# ASM2027-Rev3.net
KiCad netlist of a schematic drawn in EAGLE
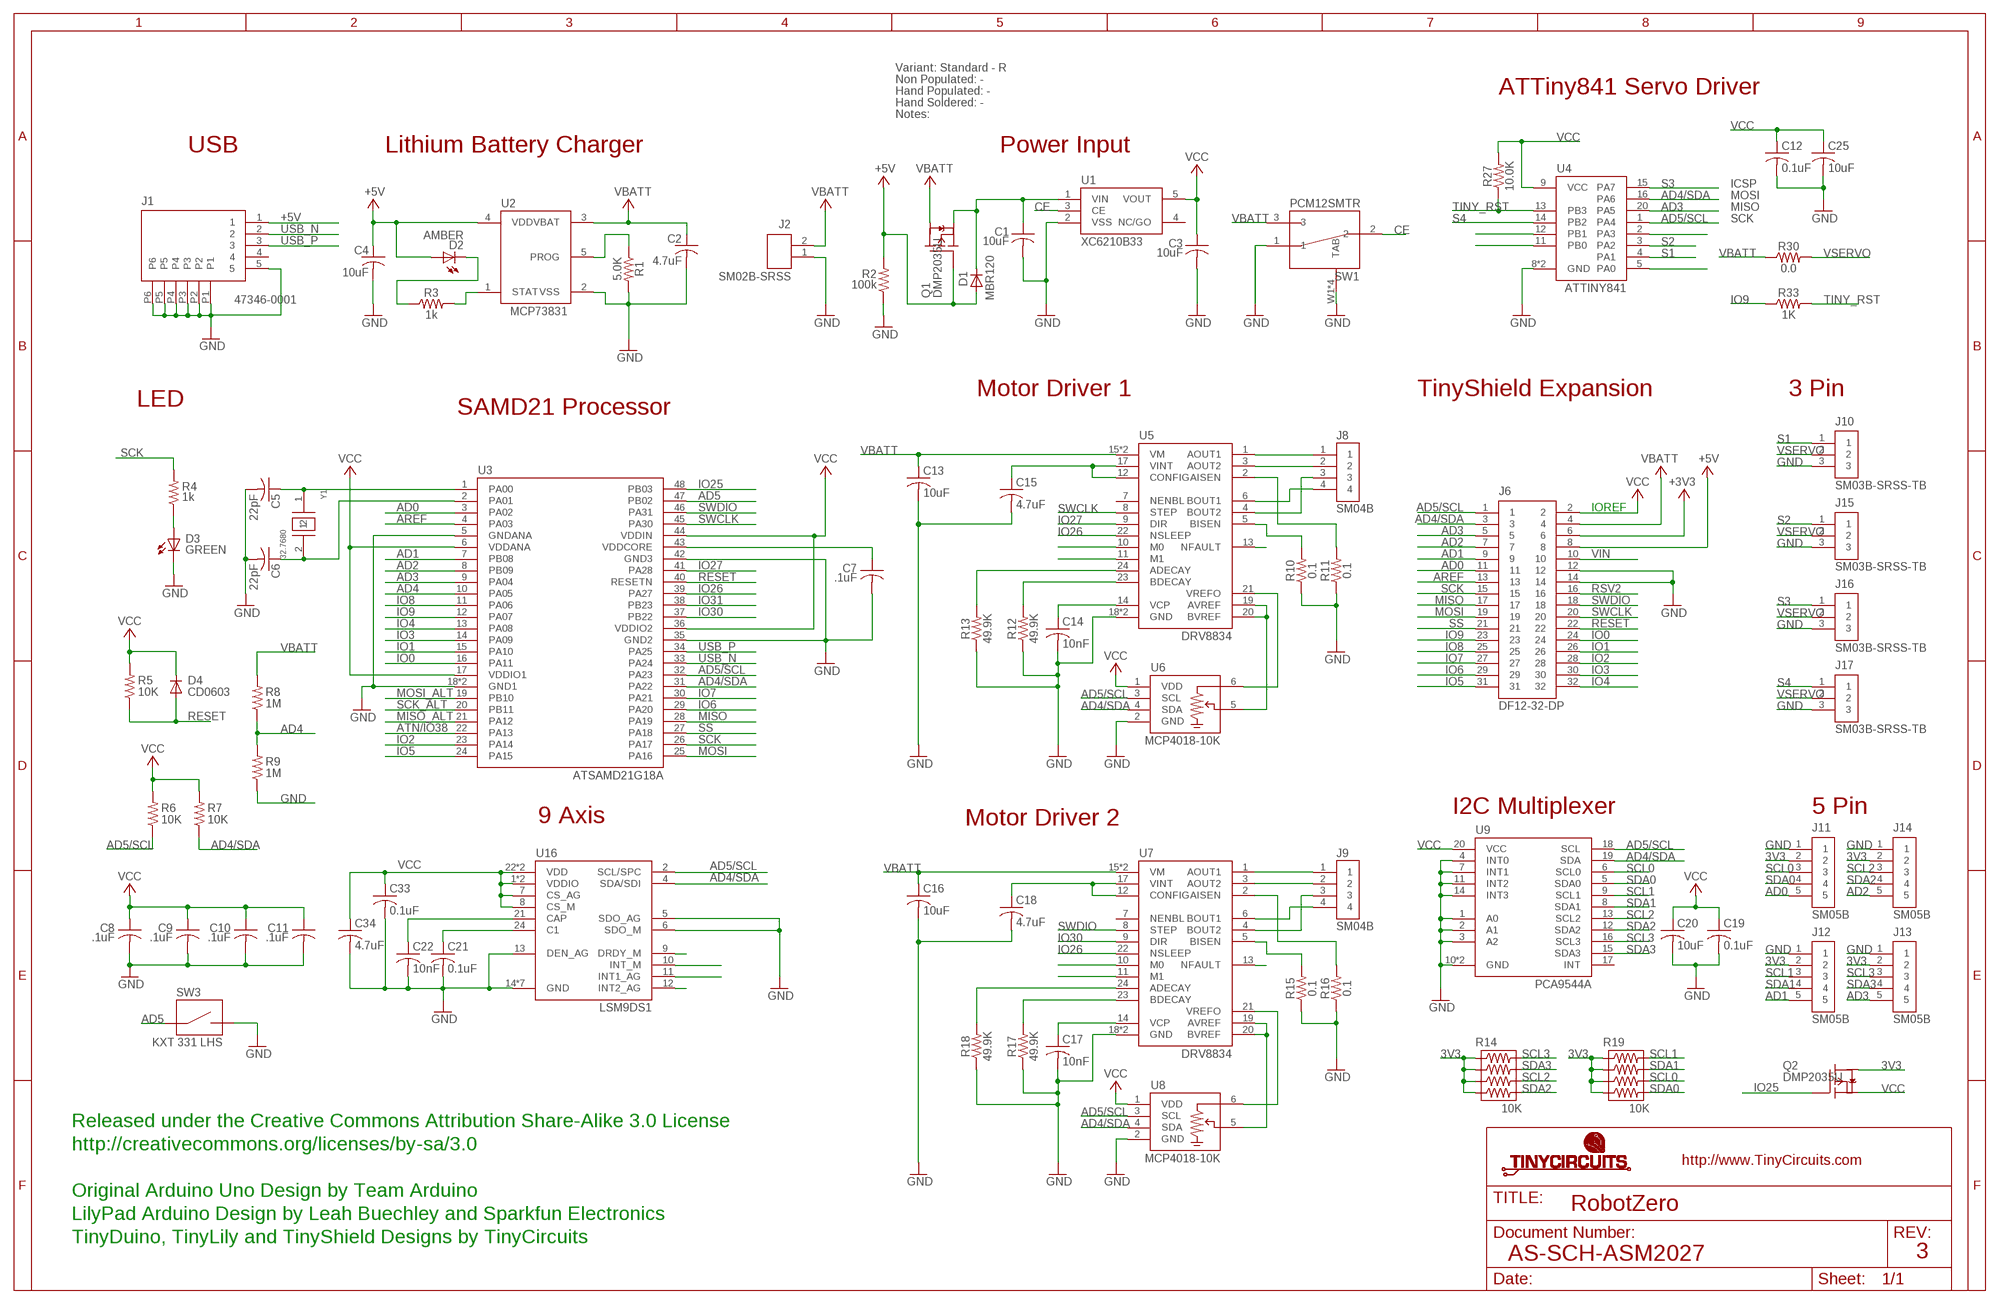
[diagram p0: schematic, sheet 1]

(export (version "E")
  (design (tool "Eeschema 10.0.6"))
  (components
    (comp (ref "C1")
      (value "10uF")
      (footprint "eagle-import:C0603")
      (fields (field (name "PARTNO") "AS-ITM-00002") (field (name "PARTNO_1") "AS-ITM-00002"))
      (libsource (lib "eagle-import") (part "AS-ITM-00002"))
    )
    (comp (ref "C2")
      (value "4.7uF")
      (footprint "eagle-import:C0603")
      (fields (field (name "PARTNO") "AS-ITM-00088") (field (name "PARTNO_1") "AS-ITM-00088"))
      (libsource (lib "eagle-import") (part "AS-ITM-00088"))
    )
    (comp (ref "C3")
      (value "10uF")
      (footprint "eagle-import:C0603")
      (fields (field (name "PARTNO") "AS-ITM-00002") (field (name "PARTNO_1") "AS-ITM-00002"))
      (libsource (lib "eagle-import") (part "AS-ITM-00002"))
    )
    (comp (ref "C4")
      (value "10uF")
      (footprint "eagle-import:C0603")
      (fields (field (name "PARTNO") "AS-ITM-00002") (field (name "PARTNO_1") "AS-ITM-00002"))
      (libsource (lib "eagle-import") (part "AS-ITM-00002"))
    )
    (comp (ref "C5")
      (value "22pF")
      (footprint "eagle-import:C0402")
      (fields (field (name "PARTNO") "AS-ITM-00211") (field (name "PARTNO_1") "AS-ITM-00211"))
      (libsource (lib "eagle-import") (part "AS-ITM-00211"))
    )
    (comp (ref "C6")
      (value "22pF")
      (footprint "eagle-import:C0402")
      (fields (field (name "PARTNO") "AS-ITM-00211") (field (name "PARTNO_1") "AS-ITM-00211"))
      (libsource (lib "eagle-import") (part "AS-ITM-00211"))
    )
    (comp (ref "C7")
      (value ".1uF")
      (footprint "eagle-import:C0402")
      (fields (field (name "PARTNO") "AS-ITM-00008") (field (name "PARTNO_1") "AS-ITM-00008"))
      (libsource (lib "eagle-import") (part "AS-ITM-00008"))
    )
    (comp (ref "C8")
      (value ".1uF")
      (footprint "eagle-import:C0402")
      (fields (field (name "PARTNO") "AS-ITM-00008") (field (name "PARTNO_1") "AS-ITM-00008"))
      (libsource (lib "eagle-import") (part "AS-ITM-00008"))
    )
    (comp (ref "C9")
      (value ".1uF")
      (footprint "eagle-import:C0402")
      (fields (field (name "PARTNO") "AS-ITM-00008") (field (name "PARTNO_1") "AS-ITM-00008"))
      (libsource (lib "eagle-import") (part "AS-ITM-00008"))
    )
    (comp (ref "C10")
      (value ".1uF")
      (footprint "eagle-import:C0402")
      (fields (field (name "PARTNO") "AS-ITM-00008") (field (name "PARTNO_1") "AS-ITM-00008"))
      (libsource (lib "eagle-import") (part "AS-ITM-00008"))
    )
    (comp (ref "C11")
      (value ".1uF")
      (footprint "eagle-import:C0402")
      (fields (field (name "PARTNO") "AS-ITM-00008") (field (name "PARTNO_1") "AS-ITM-00008"))
      (libsource (lib "eagle-import") (part "AS-ITM-00008"))
    )
    (comp (ref "C12")
      (value "0.1uF")
      (footprint "eagle-import:C0402")
      (fields (field (name "PARTNO") "AS-ITM-00008"))
      (libsource (lib "eagle-import") (part "AS-ITM-00008"))
    )
    (comp (ref "C13")
      (value "10uF")
      (footprint "eagle-import:C0603")
      (fields (field (name "PARTNO") "AS-ITM-00002"))
      (libsource (lib "eagle-import") (part "AS-ITM-00002"))
    )
    (comp (ref "C14")
      (value "10nF")
      (footprint "eagle-import:C0402")
      (fields (field (name "PARTNO") "AS-ITM-00084"))
      (libsource (lib "eagle-import") (part "AS-ITM-00084"))
    )
    (comp (ref "C15")
      (value "4.7uF")
      (footprint "eagle-import:C0402")
      (fields (field (name "PARTNO") "AS-ITM-00242"))
      (libsource (lib "eagle-import") (part "AS-ITM-00242"))
    )
    (comp (ref "C16")
      (value "10uF")
      (footprint "eagle-import:C0603")
      (fields (field (name "PARTNO") "AS-ITM-00002"))
      (libsource (lib "eagle-import") (part "AS-ITM-00002"))
    )
    (comp (ref "C17")
      (value "10nF")
      (footprint "eagle-import:C0402")
      (fields (field (name "PARTNO") "AS-ITM-00084"))
      (libsource (lib "eagle-import") (part "AS-ITM-00084"))
    )
    (comp (ref "C18")
      (value "4.7uF")
      (footprint "eagle-import:C0402")
      (fields (field (name "PARTNO") "AS-ITM-00242"))
      (libsource (lib "eagle-import") (part "AS-ITM-00242"))
    )
    (comp (ref "C19")
      (value "0.1uF")
      (footprint "eagle-import:C0402")
      (fields (field (name "PARTNO") "AS-ITM-00008"))
      (libsource (lib "eagle-import") (part "AS-ITM-00008"))
    )
    (comp (ref "C20")
      (value "10uF")
      (footprint "eagle-import:C0603")
      (fields (field (name "PARTNO") "AS-ITM-00002"))
      (libsource (lib "eagle-import") (part "AS-ITM-00002"))
    )
    (comp (ref "C21")
      (value "0.1uF")
      (footprint "eagle-import:C0402")
      (fields (field (name "PARTNO") "AS-ITM-00008"))
      (libsource (lib "eagle-import") (part "AS-ITM-00008"))
    )
    (comp (ref "C22")
      (value "10nF")
      (footprint "eagle-import:C0402")
      (fields (field (name "PARTNO") "AS-ITM-00084"))
      (libsource (lib "eagle-import") (part "AS-ITM-00084"))
    )
    (comp (ref "C25")
      (value "10uF")
      (footprint "eagle-import:C0805")
      (fields (field (name "PARTNO") "AS-ITM-00045"))
      (libsource (lib "eagle-import") (part "AS-ITM-00045"))
    )
    (comp (ref "C33")
      (value "0.1uF")
      (footprint "eagle-import:C0402")
      (fields (field (name "PARTNO") "AS-ITM-00008") (field (name "PARTNO_1") "AS-ITM-00008"))
      (libsource (lib "eagle-import") (part "AS-ITM-00008"))
    )
    (comp (ref "C34")
      (value "4.7uF")
      (footprint "eagle-import:C0402")
      (fields (field (name "PARTNO") "AS-ITM-00242") (field (name "PARTNO_1") "AS-ITM-00242"))
      (libsource (lib "eagle-import") (part "AS-ITM-00242"))
    )
    (comp (ref "D1")
      (value "MBR120")
      (footprint "eagle-import:SOD-123FL")
      (fields (field (name "PARTNO") "AS-ITM-00111"))
      (libsource (lib "eagle-import") (part "AS-ITM-00111"))
    )
    (comp (ref "D2")
      (value "AMBER")
      (footprint "eagle-import:0402_LED")
      (fields (field (name "PARTNO") "AS-ITM-00058") (field (name "PARTNO_1") "AS-ITM-00058"))
      (libsource (lib "eagle-import") (part "AS-ITM-00058"))
    )
    (comp (ref "D3")
      (value "GREEN")
      (footprint "eagle-import:LNJ_LED")
      (fields (field (name "PARTNO") "AS-ITM-00011") (field (name "PARTNO_1") "AS-ITM-00011"))
      (libsource (lib "eagle-import") (part "AS-ITM-00011"))
    )
    (comp (ref "D4")
      (value "CD0603")
      (footprint "eagle-import:0603")
      (fields (field (name "PARTNO") "AS-ITM-00009") (field (name "PARTNO_1") "AS-ITM-00009"))
      (libsource (lib "eagle-import") (part "AS-ITM-00009"))
    )
    (comp (ref "J1")
      (value "47346-0001")
      (footprint "eagle-import:MICRO_USB")
      (fields (field (name "PARTNO") "AS-ITM-00021"))
      (libsource (lib "eagle-import") (part "AS-ITM-00021"))
    )
    (comp (ref "J2")
      (value "SM02B-SRSS")
      (footprint "eagle-import:JST_SH_2X1")
      (fields (field (name "PARTNO") "AS-ITM-00231"))
      (libsource (lib "eagle-import") (part "AS-ITM-00231"))
    )
    (comp (ref "J6")
      (value "DF12-32-DP")
      (footprint "eagle-import:DF12-32-DP")
      (fields (field (name "PARTNO") "AS-ITM-00015") (field (name "PARTNO_1") "AS-ITM-00015"))
      (libsource (lib "eagle-import") (part "AS-ITM-00015"))
    )
    (comp (ref "J8")
      (value "SM04B")
      (footprint "eagle-import:JST_SH_4X1")
      (fields (field (name "PARTNO") "AS-ITM-00395") (field (name "PARTNO_1") "AS-ITM-00395"))
      (libsource (lib "eagle-import") (part "AS-ITM-00395"))
    )
    (comp (ref "J9")
      (value "SM04B")
      (footprint "eagle-import:JST_SH_4X1")
      (fields (field (name "PARTNO") "AS-ITM-00395") (field (name "PARTNO_1") "AS-ITM-00395"))
      (libsource (lib "eagle-import") (part "AS-ITM-00395"))
    )
    (comp (ref "J10")
      (value "SM03B-SRSS-TB")
      (footprint "eagle-import:JST_SH_3X1_VERT")
      (fields (field (name "PARTNO") "AS-ITM-00471") (field (name "PARTNO_1") "AS-ITM-00471"))
      (libsource (lib "eagle-import") (part "AS-ITM-00471"))
    )
    (comp (ref "J11")
      (value "SM05B")
      (footprint "eagle-import:JST_SH_5X1_VERT")
      (fields (field (name "PARTNO") "AS-ITM-00391") (field (name "PARTNO_1") "AS-ITM-00391"))
      (libsource (lib "eagle-import") (part "AS-ITM-00391"))
    )
    (comp (ref "J12")
      (value "SM05B")
      (footprint "eagle-import:JST_SH_5X1_VERT")
      (fields (field (name "PARTNO") "AS-ITM-00391") (field (name "PARTNO_1") "AS-ITM-00391"))
      (libsource (lib "eagle-import") (part "AS-ITM-00391"))
    )
    (comp (ref "J13")
      (value "SM05B")
      (footprint "eagle-import:JST_SH_5X1_VERT")
      (fields (field (name "PARTNO") "AS-ITM-00391") (field (name "PARTNO_1") "AS-ITM-00391"))
      (libsource (lib "eagle-import") (part "AS-ITM-00391"))
    )
    (comp (ref "J14")
      (value "SM05B")
      (footprint "eagle-import:JST_SH_5X1_VERT")
      (fields (field (name "PARTNO") "AS-ITM-00391") (field (name "PARTNO_1") "AS-ITM-00391"))
      (libsource (lib "eagle-import") (part "AS-ITM-00391"))
    )
    (comp (ref "J15")
      (value "SM03B-SRSS-TB")
      (footprint "eagle-import:JST_SH_3X1_VERT")
      (fields (field (name "PARTNO") "AS-ITM-00471") (field (name "PARTNO_1") "AS-ITM-00471"))
      (libsource (lib "eagle-import") (part "AS-ITM-00471"))
    )
    (comp (ref "J16")
      (value "SM03B-SRSS-TB")
      (footprint "eagle-import:JST_SH_3X1_VERT")
      (fields (field (name "PARTNO") "AS-ITM-00471") (field (name "PARTNO_1") "AS-ITM-00471"))
      (libsource (lib "eagle-import") (part "AS-ITM-00471"))
    )
    (comp (ref "J17")
      (value "SM03B-SRSS-TB")
      (footprint "eagle-import:JST_SH_3X1_VERT")
      (fields (field (name "PARTNO") "AS-ITM-00471") (field (name "PARTNO_1") "AS-ITM-00471"))
      (libsource (lib "eagle-import") (part "AS-ITM-00471"))
    )
    (comp (ref "Q1")
      (value "DMP2035U")
      (footprint "eagle-import:SOT23A")
      (fields (field (name "PARTNO") "AS-ITM-00024") (field (name "PARTNO_1") "AS-ITM-00024"))
      (libsource (lib "eagle-import") (part "AS-ITM-00024A"))
    )
    (comp (ref "Q2")
      (value "DMP2035U")
      (footprint "eagle-import:SOT23A")
      (fields (field (name "PARTNO") "AS-ITM-00024") (field (name "PARTNO_1") "AS-ITM-00024"))
      (libsource (lib "eagle-import") (part "AS-ITM-00024A"))
    )
    (comp (ref "R1")
      (value "5.0K")
      (footprint "eagle-import:0402")
      (fields (field (name "PARTNO") "AS-ITM-00289") (field (name "PARTNO_1") "AS-ITM-00289"))
      (libsource (lib "eagle-import") (part "AS-ITM-00289"))
    )
    (comp (ref "R2")
      (value "100k")
      (footprint "eagle-import:0402")
      (fields (field (name "PARTNO") "AS-ITM-00004") (field (name "PARTNO_1") "AS-ITM-00004"))
      (libsource (lib "eagle-import") (part "AS-ITM-00004"))
    )
    (comp (ref "R3")
      (value "1k")
      (footprint "eagle-import:0402")
      (fields (field (name "PARTNO") "AS-ITM-00003") (field (name "PARTNO_1") "AS-ITM-00003"))
      (libsource (lib "eagle-import") (part "AS-ITM-00003"))
    )
    (comp (ref "R4")
      (value "1k")
      (footprint "eagle-import:0402")
      (fields (field (name "PARTNO") "AS-ITM-00003") (field (name "PARTNO_1") "AS-ITM-00003"))
      (libsource (lib "eagle-import") (part "AS-ITM-00003"))
    )
    (comp (ref "R5")
      (value "10K")
      (footprint "eagle-import:0402")
      (fields (field (name "PARTNO") "AS-ITM-00032") (field (name "PARTNO_1") "AS-ITM-00032"))
      (libsource (lib "eagle-import") (part "AS-ITM-00032"))
    )
    (comp (ref "R6")
      (value "10K")
      (footprint "eagle-import:0402")
      (fields (field (name "PARTNO") "AS-ITM-00032") (field (name "PARTNO_1") "AS-ITM-00032"))
      (libsource (lib "eagle-import") (part "AS-ITM-00032"))
    )
    (comp (ref "R7")
      (value "10K")
      (footprint "eagle-import:0402")
      (fields (field (name "PARTNO") "AS-ITM-00032") (field (name "PARTNO_1") "AS-ITM-00032"))
      (libsource (lib "eagle-import") (part "AS-ITM-00032"))
    )
    (comp (ref "R8")
      (value "1M")
      (footprint "eagle-import:0402")
      (fields (field (name "PARTNO") "AS-ITM-00005") (field (name "PARTNO_1") "AS-ITM-00005"))
      (libsource (lib "eagle-import") (part "AS-ITM-00005"))
    )
    (comp (ref "R9")
      (value "1M")
      (footprint "eagle-import:0402")
      (fields (field (name "PARTNO") "AS-ITM-00005") (field (name "PARTNO_1") "AS-ITM-00005"))
      (libsource (lib "eagle-import") (part "AS-ITM-00005"))
    )
    (comp (ref "R10")
      (value "0.1")
      (footprint "eagle-import:R0805")
      (fields (field (name "PARTNO") "AS-ITM-00157"))
      (libsource (lib "eagle-import") (part "AS-ITM-00157"))
    )
    (comp (ref "R11")
      (value "0.1")
      (footprint "eagle-import:R0805")
      (fields (field (name "PARTNO") "AS-ITM-00157"))
      (libsource (lib "eagle-import") (part "AS-ITM-00157"))
    )
    (comp (ref "R12")
      (value "49.9K")
      (footprint "eagle-import:0402")
      (fields (field (name "PARTNO") "AS-ITM-00074"))
      (libsource (lib "eagle-import") (part "AS-ITM-00074"))
    )
    (comp (ref "R13")
      (value "49.9K")
      (footprint "eagle-import:0402")
      (fields (field (name "PARTNO") "AS-ITM-00074"))
      (libsource (lib "eagle-import") (part "AS-ITM-00074"))
    )
    (comp (ref "R14")
      (value "10K")
      (footprint "eagle-import:0402RPACK")
      (fields (field (name "PARTNO") "AS-ITM-00520") (field (name "PARTNO_1") "AS-ITM-00520"))
      (libsource (lib "eagle-import") (part "AS-ITM-00520"))
    )
    (comp (ref "R15")
      (value "0.1")
      (footprint "eagle-import:R0805")
      (fields (field (name "PARTNO") "AS-ITM-00157"))
      (libsource (lib "eagle-import") (part "AS-ITM-00157"))
    )
    (comp (ref "R16")
      (value "0.1")
      (footprint "eagle-import:R0805")
      (fields (field (name "PARTNO") "AS-ITM-00157"))
      (libsource (lib "eagle-import") (part "AS-ITM-00157"))
    )
    (comp (ref "R17")
      (value "49.9K")
      (footprint "eagle-import:0402")
      (fields (field (name "PARTNO") "AS-ITM-00074"))
      (libsource (lib "eagle-import") (part "AS-ITM-00074"))
    )
    (comp (ref "R18")
      (value "49.9K")
      (footprint "eagle-import:0402")
      (fields (field (name "PARTNO") "AS-ITM-00074"))
      (libsource (lib "eagle-import") (part "AS-ITM-00074"))
    )
    (comp (ref "R19")
      (value "10K")
      (footprint "eagle-import:0402RPACK")
      (fields (field (name "PARTNO") "AS-ITM-00520") (field (name "PARTNO_1") "AS-ITM-00520"))
      (libsource (lib "eagle-import") (part "AS-ITM-00520"))
    )
    (comp (ref "R27")
      (value "10.0K")
      (footprint "eagle-import:0402")
      (fields (field (name "PARTNO") "AS-ITM-00032"))
      (libsource (lib "eagle-import") (part "AS-ITM-00032"))
    )
    (comp (ref "R30")
      (value "0.0")
      (footprint "eagle-import:0402")
      (fields (field (name "PARTNO") "AS-ITM-00076"))
      (libsource (lib "eagle-import") (part "AS-ITM-00076"))
    )
    (comp (ref "R33")
      (value "1K")
      (footprint "eagle-import:0402")
      (fields (field (name "PARTNO") "AS-ITM-00003"))
      (libsource (lib "eagle-import") (part "AS-ITM-00003"))
    )
    (comp (ref "SW1")
      (value "PCM12SMTR")
      (footprint "eagle-import:PCM12SMTR")
      (fields (field (name "PARTNO") "AS-ITM-00220"))
      (libsource (lib "eagle-import") (part "AS-ITM-00220"))
    )
    (comp (ref "SW3")
      (value "KXT 331 LHS")
      (footprint "eagle-import:KXT_LHS")
      (fields (field (name "PARTNO") "AS-ITM-00372"))
      (libsource (lib "eagle-import") (part "AS-ITM-00372"))
    )
    (comp (ref "U1")
      (value "XC6210B33")
      (footprint "eagle-import:SOT-25")
      (fields (field (name "PARTNO") "AS-ITM-00046"))
      (libsource (lib "eagle-import") (part "AS-ITM-00046"))
    )
    (comp (ref "U2")
      (value "MCP73831")
      (footprint "eagle-import:SOT-23")
      (fields (field (name "PARTNO") "AS-ITM-00136"))
      (libsource (lib "eagle-import") (part "AS-ITM-00136"))
    )
    (comp (ref "U3")
      (value "ATSAMD21G18A")
      (footprint "eagle-import:QFN48")
      (fields (field (name "PARTNO") "AS-ITM-00273") (field (name "PARTNO_1") "AS-ITM-00273"))
      (libsource (lib "eagle-import") (part "AS-ITM-00273"))
    )
    (comp (ref "U4")
      (value "ATTINY841")
      (footprint "eagle-import:VQFN-20")
      (fields (field (name "PARTNO") "AS-ITM-00255"))
      (libsource (lib "eagle-import") (part "AS-ITM-00255"))
    )
    (comp (ref "U5")
      (value "DRV8834")
      (footprint "eagle-import:VQFN-24_4X4")
      (fields (field (name "PARTNO") "AS-ITM-00392"))
      (libsource (lib "eagle-import") (part "AS-ITM-00392"))
    )
    (comp (ref "U6")
      (value "MCP4018-10K")
      (footprint "eagle-import:SOT-353-6")
      (fields (field (name "PARTNO") "AS-ITM-00393"))
      (libsource (lib "eagle-import") (part "AS-ITM-00393"))
    )
    (comp (ref "U7")
      (value "DRV8834")
      (footprint "eagle-import:VQFN-24_4X4")
      (fields (field (name "PARTNO") "AS-ITM-00392"))
      (libsource (lib "eagle-import") (part "AS-ITM-00392"))
    )
    (comp (ref "U8")
      (value "MCP4018-10K")
      (footprint "eagle-import:SOT-353-6")
      (fields (field (name "PARTNO") "AS-ITM-00393"))
      (libsource (lib "eagle-import") (part "AS-ITM-00393"))
    )
    (comp (ref "U9")
      (value "PCA9544A")
      (footprint "eagle-import:VQFN-20_4.5X3.5")
      (fields (field (name "PARTNO") "AS-ITM-00342"))
      (libsource (lib "eagle-import") (part "AS-ITM-00342"))
    )
    (comp (ref "U16")
      (value "LSM9DS1")
      (footprint "eagle-import:LGA-24")
      (fields (field (name "PARTNO") "AS-ITM-00265"))
      (libsource (lib "eagle-import") (part "AS-ITM-00265"))
    )
    (comp (ref "Y1")
      (value "32.7680")
      (footprint "eagle-import:ABS06")
      (fields (field (name "PARTNO") "AS-ITM-00279") (field (name "PARTNO_1") "AS-ITM-00279"))
      (libsource (lib "eagle-import") (part "AS-ITM-00279"))
    )
  )
  (nets
    (net (code "1") (name "+3V3") (class "Default")
      (node (ref "J6") (pin "6") (pinfunction "6_6") (pintype "bidirectional"))
    )
    (net (code "2") (name "+5V") (class "Default")
      (node (ref "C4") (pin "1") (pinfunction "1_1") (pintype "passive"))
      (node (ref "D1") (pin "A") (pinfunction "A_A") (pintype "passive"))
      (node (ref "D2") (pin "1") (pinfunction "A_1") (pintype "passive"))
      (node (ref "J1") (pin "1") (pinfunction "1_1") (pintype "bidirectional"))
      (node (ref "J6") (pin "8") (pinfunction "8_8") (pintype "bidirectional"))
      (node (ref "Q1") (pin "B") (pinfunction "G_B") (pintype "passive"))
      (node (ref "R2") (pin "2") (pinfunction "2_2") (pintype "passive"))
      (node (ref "U2") (pin "4") (pinfunction "VDD_4") (pintype "bidirectional"))
    )
    (net (code "3") (name "/3V3") (class "Default")
      (node (ref "J11") (pin "2") (pinfunction "2_2") (pintype "bidirectional"))
      (node (ref "J12") (pin "2") (pinfunction "2_2") (pintype "bidirectional"))
      (node (ref "J13") (pin "2") (pinfunction "2_2") (pintype "bidirectional"))
      (node (ref "J14") (pin "2") (pinfunction "2_2") (pintype "bidirectional"))
      (node (ref "Q2") (pin "C") (pinfunction "D_C") (pintype "passive"))
      (node (ref "R14") (pin "1") (pinfunction "1_1") (pintype "passive"))
      (node (ref "R14") (pin "3") (pinfunction "3_3") (pintype "passive"))
      (node (ref "R14") (pin "5") (pinfunction "5_5") (pintype "passive"))
      (node (ref "R14") (pin "7") (pinfunction "7_7") (pintype "passive"))
      (node (ref "R19") (pin "1") (pinfunction "1_1") (pintype "passive"))
      (node (ref "R19") (pin "3") (pinfunction "3_3") (pintype "passive"))
      (node (ref "R19") (pin "5") (pinfunction "5_5") (pintype "passive"))
      (node (ref "R19") (pin "7") (pinfunction "7_7") (pintype "passive"))
    )
    (net (code "4") (name "/AD0") (class "Default")
      (node (ref "J11") (pin "5") (pinfunction "5_5") (pintype "bidirectional"))
      (node (ref "J6") (pin "11") (pinfunction "11_11") (pintype "bidirectional"))
      (node (ref "U3") (pin "3") (pinfunction "PA02_3") (pintype "bidirectional"))
    )
    (net (code "5") (name "/AD1") (class "Default")
      (node (ref "J12") (pin "5") (pinfunction "5_5") (pintype "bidirectional"))
      (node (ref "J6") (pin "9") (pinfunction "9_9") (pintype "bidirectional"))
      (node (ref "U3") (pin "7") (pinfunction "PB08_7") (pintype "bidirectional"))
    )
    (net (code "6") (name "/AD2") (class "Default")
      (node (ref "J14") (pin "5") (pinfunction "5_5") (pintype "bidirectional"))
      (node (ref "J6") (pin "7") (pinfunction "7_7") (pintype "bidirectional"))
      (node (ref "U3") (pin "8") (pinfunction "PB09_8") (pintype "bidirectional"))
    )
    (net (code "7") (name "/AD3") (class "Default")
      (node (ref "J13") (pin "5") (pinfunction "5_5") (pintype "bidirectional"))
      (node (ref "J6") (pin "5") (pinfunction "5_5") (pintype "bidirectional"))
      (node (ref "U3") (pin "9") (pinfunction "PA04_9") (pintype "bidirectional"))
      (node (ref "U4") (pin "20") (pinfunction "PA5_20") (pintype "bidirectional"))
    )
    (net (code "8") (name "/AD4") (class "Default")
      (node (ref "R8") (pin "1") (pinfunction "1_1") (pintype "passive"))
      (node (ref "R9") (pin "2") (pinfunction "2_2") (pintype "passive"))
      (node (ref "U3") (pin "10") (pinfunction "PA05_10") (pintype "bidirectional"))
    )
    (net (code "9") (name "/AD4{slash}SDA") (class "Default")
      (node (ref "J6") (pin "3") (pinfunction "3_3") (pintype "bidirectional"))
      (node (ref "R7") (pin "1") (pinfunction "1_1") (pintype "passive"))
      (node (ref "U16") (pin "4") (pinfunction "SDA/SDI_4") (pintype "bidirectional"))
      (node (ref "U3") (pin "31") (pinfunction "PA22_31") (pintype "bidirectional"))
      (node (ref "U4") (pin "16") (pinfunction "PA6_16") (pintype "bidirectional"))
      (node (ref "U6") (pin "4") (pinfunction "SDA_4") (pintype "bidirectional"))
      (node (ref "U8") (pin "4") (pinfunction "SDA_4") (pintype "bidirectional"))
      (node (ref "U9") (pin "19") (pinfunction "SDA_19") (pintype "bidirectional"))
    )
    (net (code "10") (name "/AD5") (class "Default")
      (node (ref "SW3") (pin "1") (pinfunction "1_1") (pintype "bidirectional"))
      (node (ref "U3") (pin "47") (pinfunction "PB02_47") (pintype "bidirectional"))
    )
    (net (code "11") (name "/AD5{slash}SCL") (class "Default")
      (node (ref "J6") (pin "1") (pinfunction "1_1") (pintype "bidirectional"))
      (node (ref "R6") (pin "1") (pinfunction "1_1") (pintype "passive"))
      (node (ref "U16") (pin "2") (pinfunction "SCL/SPC_2") (pintype "bidirectional"))
      (node (ref "U3") (pin "32") (pinfunction "PA23_32") (pintype "bidirectional"))
      (node (ref "U4") (pin "1") (pinfunction "PA4_1") (pintype "bidirectional"))
      (node (ref "U6") (pin "3") (pinfunction "SCL_3") (pintype "bidirectional"))
      (node (ref "U8") (pin "3") (pinfunction "SCL_3") (pintype "bidirectional"))
      (node (ref "U9") (pin "18") (pinfunction "SCL_18") (pintype "bidirectional"))
    )
    (net (code "12") (name "/AREF") (class "Default")
      (node (ref "J6") (pin "13") (pinfunction "13_13") (pintype "bidirectional"))
      (node (ref "U3") (pin "4") (pinfunction "PA03_4") (pintype "bidirectional"))
    )
    (net (code "13") (name "/ATN{slash}IO38") (class "Default")
      (node (ref "U3") (pin "22") (pinfunction "PA13_22") (pintype "bidirectional"))
    )
    (net (code "14") (name "/CE") (class "Default")
      (node (ref "SW1") (pin "2") (pinfunction "2_2") (pintype "bidirectional"))
      (node (ref "U1") (pin "3") (pinfunction "CE_3") (pintype "bidirectional"))
    )
    (net (code "15") (name "/IO0") (class "Default")
      (node (ref "J6") (pin "24") (pinfunction "24_24") (pintype "bidirectional"))
      (node (ref "U3") (pin "16") (pinfunction "PA11_16") (pintype "bidirectional"))
    )
    (net (code "16") (name "/IO1") (class "Default")
      (node (ref "J6") (pin "26") (pinfunction "26_26") (pintype "bidirectional"))
      (node (ref "U3") (pin "15") (pinfunction "PA10_15") (pintype "bidirectional"))
    )
    (net (code "17") (name "/IO2") (class "Default")
      (node (ref "J6") (pin "28") (pinfunction "28_28") (pintype "bidirectional"))
      (node (ref "U3") (pin "23") (pinfunction "PA14_23") (pintype "bidirectional"))
    )
    (net (code "18") (name "/IO3") (class "Default")
      (node (ref "J6") (pin "30") (pinfunction "30_30") (pintype "bidirectional"))
      (node (ref "U3") (pin "14") (pinfunction "PA09_14") (pintype "bidirectional"))
    )
    (net (code "19") (name "/IO4") (class "Default")
      (node (ref "J6") (pin "32") (pinfunction "32_32") (pintype "bidirectional"))
      (node (ref "U3") (pin "13") (pinfunction "PA08_13") (pintype "bidirectional"))
    )
    (net (code "20") (name "/IO5") (class "Default")
      (node (ref "J6") (pin "31") (pinfunction "31_31") (pintype "bidirectional"))
      (node (ref "U3") (pin "24") (pinfunction "PA15_24") (pintype "bidirectional"))
    )
    (net (code "21") (name "/IO6") (class "Default")
      (node (ref "J6") (pin "29") (pinfunction "29_29") (pintype "bidirectional"))
      (node (ref "U3") (pin "29") (pinfunction "PA20_29") (pintype "bidirectional"))
    )
    (net (code "22") (name "/IO7") (class "Default")
      (node (ref "J6") (pin "27") (pinfunction "27_27") (pintype "bidirectional"))
      (node (ref "U3") (pin "30") (pinfunction "PA21_30") (pintype "bidirectional"))
    )
    (net (code "23") (name "/IO8") (class "Default")
      (node (ref "J6") (pin "25") (pinfunction "25_25") (pintype "bidirectional"))
      (node (ref "U3") (pin "11") (pinfunction "PA06_11") (pintype "bidirectional"))
    )
    (net (code "24") (name "/IO9") (class "Default")
      (node (ref "J6") (pin "23") (pinfunction "23_23") (pintype "bidirectional"))
      (node (ref "R33") (pin "1") (pinfunction "1_1") (pintype "passive"))
      (node (ref "U3") (pin "12") (pinfunction "PA07_12") (pintype "bidirectional"))
    )
    (net (code "25") (name "/IO25") (class "Default")
      (node (ref "Q2") (pin "B") (pinfunction "G_B") (pintype "passive"))
      (node (ref "U3") (pin "48") (pinfunction "PB03_48") (pintype "bidirectional"))
    )
    (net (code "26") (name "/IO26") (class "Default")
      (node (ref "U3") (pin "39") (pinfunction "PA27_39") (pintype "bidirectional"))
      (node (ref "U5") (pin "22") (pinfunction "NSLEEP_22") (pintype "bidirectional"))
      (node (ref "U7") (pin "22") (pinfunction "NSLEEP_22") (pintype "bidirectional"))
    )
    (net (code "27") (name "/IO27") (class "Default")
      (node (ref "U3") (pin "41") (pinfunction "PA28_41") (pintype "bidirectional"))
      (node (ref "U5") (pin "9") (pinfunction "DIR_9") (pintype "bidirectional"))
    )
    (net (code "28") (name "/IO30") (class "Default")
      (node (ref "U3") (pin "37") (pinfunction "PB22_37") (pintype "bidirectional"))
      (node (ref "U7") (pin "9") (pinfunction "DIR_9") (pintype "bidirectional"))
    )
    (net (code "29") (name "/IO31") (class "Default")
      (node (ref "U3") (pin "38") (pinfunction "PB23_38") (pintype "bidirectional"))
    )
    (net (code "30") (name "/MISO") (class "Default")
      (node (ref "J6") (pin "17") (pinfunction "17_17") (pintype "bidirectional"))
      (node (ref "U3") (pin "28") (pinfunction "PA19_28") (pintype "bidirectional"))
    )
    (net (code "31") (name "/MISO_ALT") (class "Default")
      (node (ref "U3") (pin "21") (pinfunction "PA12_21") (pintype "bidirectional"))
    )
    (net (code "32") (name "/MOSI") (class "Default")
      (node (ref "J6") (pin "19") (pinfunction "19_19") (pintype "bidirectional"))
      (node (ref "U3") (pin "25") (pinfunction "PA16_25") (pintype "bidirectional"))
    )
    (net (code "33") (name "/MOSI_ALT") (class "Default")
      (node (ref "U3") (pin "19") (pinfunction "PB10_19") (pintype "bidirectional"))
    )
    (net (code "34") (name "/RESET") (class "Default")
      (node (ref "D4") (pin "A") (pinfunction "A_A") (pintype "passive"))
      (node (ref "J6") (pin "22") (pinfunction "22_22") (pintype "bidirectional"))
      (node (ref "R5") (pin "1") (pinfunction "1_1") (pintype "passive"))
      (node (ref "U3") (pin "40") (pinfunction "RESETN_40") (pintype "bidirectional"))
    )
    (net (code "35") (name "/RSV2") (class "Default")
      (node (ref "J6") (pin "16") (pinfunction "16_16") (pintype "bidirectional"))
    )
    (net (code "36") (name "/S1") (class "Default")
      (node (ref "J10") (pin "1") (pinfunction "1_1") (pintype "bidirectional"))
      (node (ref "U4") (pin "4") (pinfunction "PA1_4") (pintype "bidirectional"))
    )
    (net (code "37") (name "/S2") (class "Default")
      (node (ref "J15") (pin "1") (pinfunction "1_1") (pintype "bidirectional"))
      (node (ref "U4") (pin "3") (pinfunction "PA2_3") (pintype "bidirectional"))
    )
    (net (code "38") (name "/S3") (class "Default")
      (node (ref "J16") (pin "1") (pinfunction "1_1") (pintype "bidirectional"))
      (node (ref "U4") (pin "15") (pinfunction "PA7_15") (pintype "bidirectional"))
    )
    (net (code "39") (name "/S4") (class "Default")
      (node (ref "J17") (pin "1") (pinfunction "1_1") (pintype "bidirectional"))
      (node (ref "U4") (pin "14") (pinfunction "PB2_14") (pintype "bidirectional"))
    )
    (net (code "40") (name "/SCK") (class "Default")
      (node (ref "J6") (pin "15") (pinfunction "15_15") (pintype "bidirectional"))
      (node (ref "R4") (pin "2") (pinfunction "2_2") (pintype "passive"))
      (node (ref "U3") (pin "26") (pinfunction "PA17_26") (pintype "bidirectional"))
    )
    (net (code "41") (name "/SCK_ALT") (class "Default")
      (node (ref "U3") (pin "20") (pinfunction "PB11_20") (pintype "bidirectional"))
    )
    (net (code "42") (name "/SCL0") (class "Default")
      (node (ref "J11") (pin "3") (pinfunction "3_3") (pintype "bidirectional"))
      (node (ref "R19") (pin "6") (pinfunction "6_6") (pintype "passive"))
      (node (ref "U9") (pin "6") (pinfunction "SCL0_6") (pintype "bidirectional"))
    )
    (net (code "43") (name "/SCL1") (class "Default")
      (node (ref "J12") (pin "3") (pinfunction "3_3") (pintype "bidirectional"))
      (node (ref "R19") (pin "2") (pinfunction "2_2") (pintype "passive"))
      (node (ref "U9") (pin "9") (pinfunction "SCL1_9") (pintype "bidirectional"))
    )
    (net (code "44") (name "/SCL2") (class "Default")
      (node (ref "J14") (pin "3") (pinfunction "3_3") (pintype "bidirectional"))
      (node (ref "R14") (pin "6") (pinfunction "6_6") (pintype "passive"))
      (node (ref "U9") (pin "13") (pinfunction "SCL2_13") (pintype "bidirectional"))
    )
    (net (code "45") (name "/SCL3") (class "Default")
      (node (ref "J13") (pin "3") (pinfunction "3_3") (pintype "bidirectional"))
      (node (ref "R14") (pin "2") (pinfunction "2_2") (pintype "passive"))
      (node (ref "U9") (pin "16") (pinfunction "SCL3_16") (pintype "bidirectional"))
    )
    (net (code "46") (name "/SDA0") (class "Default")
      (node (ref "J11") (pin "4") (pinfunction "4_4") (pintype "bidirectional"))
      (node (ref "R19") (pin "8") (pinfunction "8_8") (pintype "passive"))
      (node (ref "U9") (pin "5") (pinfunction "SDA0_5") (pintype "bidirectional"))
    )
    (net (code "47") (name "/SDA1") (class "Default")
      (node (ref "J12") (pin "4") (pinfunction "4_4") (pintype "bidirectional"))
      (node (ref "R19") (pin "4") (pinfunction "4_4") (pintype "passive"))
      (node (ref "U9") (pin "8") (pinfunction "SDA1_8") (pintype "bidirectional"))
    )
    (net (code "48") (name "/SDA2") (class "Default")
      (node (ref "J14") (pin "4") (pinfunction "4_4") (pintype "bidirectional"))
      (node (ref "R14") (pin "8") (pinfunction "8_8") (pintype "passive"))
      (node (ref "U9") (pin "12") (pinfunction "SDA2_12") (pintype "bidirectional"))
    )
    (net (code "49") (name "/SDA3") (class "Default")
      (node (ref "J13") (pin "4") (pinfunction "4_4") (pintype "bidirectional"))
      (node (ref "R14") (pin "4") (pinfunction "4_4") (pintype "passive"))
      (node (ref "U9") (pin "15") (pinfunction "SDA3_15") (pintype "bidirectional"))
    )
    (net (code "50") (name "/SS") (class "Default")
      (node (ref "J6") (pin "21") (pinfunction "21_21") (pintype "bidirectional"))
      (node (ref "U3") (pin "27") (pinfunction "PA18_27") (pintype "bidirectional"))
    )
    (net (code "51") (name "/SWCLK") (class "Default")
      (node (ref "J6") (pin "20") (pinfunction "20_20") (pintype "bidirectional"))
      (node (ref "U3") (pin "45") (pinfunction "PA30_45") (pintype "bidirectional"))
      (node (ref "U5") (pin "8") (pinfunction "STEP_8") (pintype "bidirectional"))
    )
    (net (code "52") (name "/SWDIO") (class "Default")
      (node (ref "J6") (pin "18") (pinfunction "18_18") (pintype "bidirectional"))
      (node (ref "U3") (pin "46") (pinfunction "PA31_46") (pintype "bidirectional"))
      (node (ref "U7") (pin "8") (pinfunction "STEP_8") (pintype "bidirectional"))
    )
    (net (code "53") (name "/TINY_RST") (class "Default")
      (node (ref "R27") (pin "1") (pinfunction "1_1") (pintype "passive"))
      (node (ref "R33") (pin "2") (pinfunction "2_2") (pintype "passive"))
      (node (ref "U4") (pin "13") (pinfunction "PB3_13") (pintype "bidirectional"))
    )
    (net (code "54") (name "/USB_N") (class "Default")
      (node (ref "J1") (pin "2") (pinfunction "2_2") (pintype "bidirectional"))
      (node (ref "U3") (pin "33") (pinfunction "PA24_33") (pintype "bidirectional"))
    )
    (net (code "55") (name "/USB_P") (class "Default")
      (node (ref "J1") (pin "3") (pinfunction "3_3") (pintype "bidirectional"))
      (node (ref "U3") (pin "34") (pinfunction "PA25_34") (pintype "bidirectional"))
    )
    (net (code "56") (name "/VIN") (class "Default")
      (node (ref "J6") (pin "10") (pinfunction "10_10") (pintype "bidirectional"))
    )
    (net (code "57") (name "/VSERVO") (class "Default")
      (node (ref "J10") (pin "2") (pinfunction "2_2") (pintype "bidirectional"))
      (node (ref "J15") (pin "2") (pinfunction "2_2") (pintype "bidirectional"))
      (node (ref "J16") (pin "2") (pinfunction "2_2") (pintype "bidirectional"))
      (node (ref "J17") (pin "2") (pinfunction "2_2") (pintype "bidirectional"))
      (node (ref "R30") (pin "2") (pinfunction "2_2") (pintype "passive"))
    )
    (net (code "58") (name "GND") (class "Default")
      (node (ref "C1") (pin "2") (pinfunction "2_2") (pintype "passive"))
      (node (ref "C10") (pin "2") (pinfunction "2_2") (pintype "passive"))
      (node (ref "C11") (pin "2") (pinfunction "2_2") (pintype "passive"))
      (node (ref "C12") (pin "2") (pinfunction "2_2") (pintype "passive"))
      (node (ref "C13") (pin "2") (pinfunction "2_2") (pintype "passive"))
      (node (ref "C14") (pin "2") (pinfunction "2_2") (pintype "passive"))
      (node (ref "C15") (pin "2") (pinfunction "2_2") (pintype "passive"))
      (node (ref "C16") (pin "2") (pinfunction "2_2") (pintype "passive"))
      (node (ref "C17") (pin "2") (pinfunction "2_2") (pintype "passive"))
      (node (ref "C18") (pin "2") (pinfunction "2_2") (pintype "passive"))
      (node (ref "C19") (pin "2") (pinfunction "2_2") (pintype "passive"))
      (node (ref "C2") (pin "2") (pinfunction "2_2") (pintype "passive"))
      (node (ref "C20") (pin "2") (pinfunction "2_2") (pintype "passive"))
      (node (ref "C21") (pin "2") (pinfunction "2_2") (pintype "passive"))
      (node (ref "C22") (pin "2") (pinfunction "2_2") (pintype "passive"))
      (node (ref "C25") (pin "2") (pinfunction "2_2") (pintype "passive"))
      (node (ref "C3") (pin "2") (pinfunction "2_2") (pintype "passive"))
      (node (ref "C33") (pin "2") (pinfunction "2_2") (pintype "passive"))
      (node (ref "C34") (pin "2") (pinfunction "2_2") (pintype "passive"))
      (node (ref "C4") (pin "2") (pinfunction "2_2") (pintype "passive"))
      (node (ref "C5") (pin "2") (pinfunction "2_2") (pintype "passive"))
      (node (ref "C6") (pin "2") (pinfunction "2_2") (pintype "passive"))
      (node (ref "C7") (pin "2") (pinfunction "2_2") (pintype "passive"))
      (node (ref "C8") (pin "2") (pinfunction "2_2") (pintype "passive"))
      (node (ref "C9") (pin "2") (pinfunction "2_2") (pintype "passive"))
      (node (ref "D3") (pin "C") (pinfunction "C_C") (pintype "passive"))
      (node (ref "J1") (pin "5") (pinfunction "5_5") (pintype "bidirectional"))
      (node (ref "J1") (pin "P1") (pinfunction "P1_P1") (pintype "bidirectional"))
      (node (ref "J1") (pin "P2") (pinfunction "P2_P2") (pintype "bidirectional"))
      (node (ref "J1") (pin "P3") (pinfunction "P3_P3") (pintype "bidirectional"))
      (node (ref "J1") (pin "P4") (pinfunction "P4_P4") (pintype "bidirectional"))
      (node (ref "J1") (pin "P5") (pinfunction "P5_P5") (pintype "bidirectional"))
      (node (ref "J1") (pin "P6") (pinfunction "P6_P6") (pintype "bidirectional"))
      (node (ref "J10") (pin "3") (pinfunction "3_3") (pintype "bidirectional"))
      (node (ref "J11") (pin "1") (pinfunction "1_1") (pintype "bidirectional"))
      (node (ref "J12") (pin "1") (pinfunction "1_1") (pintype "bidirectional"))
      (node (ref "J13") (pin "1") (pinfunction "1_1") (pintype "bidirectional"))
      (node (ref "J14") (pin "1") (pinfunction "1_1") (pintype "bidirectional"))
      (node (ref "J15") (pin "3") (pinfunction "3_3") (pintype "bidirectional"))
      (node (ref "J16") (pin "3") (pinfunction "3_3") (pintype "bidirectional"))
      (node (ref "J17") (pin "3") (pinfunction "3_3") (pintype "bidirectional"))
      (node (ref "J2") (pin "1") (pinfunction "2_1") (pintype "bidirectional"))
      (node (ref "J6") (pin "12") (pinfunction "12_12") (pintype "bidirectional"))
      (node (ref "J6") (pin "14") (pinfunction "14_14") (pintype "bidirectional"))
      (node (ref "R1") (pin "2") (pinfunction "2_2") (pintype "passive"))
      (node (ref "R10") (pin "1") (pinfunction "1_1") (pintype "passive"))
      (node (ref "R11") (pin "1") (pinfunction "1_1") (pintype "passive"))
      (node (ref "R12") (pin "1") (pinfunction "1_1") (pintype "passive"))
      (node (ref "R13") (pin "1") (pinfunction "1_1") (pintype "passive"))
      (node (ref "R15") (pin "1") (pinfunction "1_1") (pintype "passive"))
      (node (ref "R16") (pin "1") (pinfunction "1_1") (pintype "passive"))
      (node (ref "R17") (pin "1") (pinfunction "1_1") (pintype "passive"))
      (node (ref "R18") (pin "1") (pinfunction "1_1") (pintype "passive"))
      (node (ref "R2") (pin "1") (pinfunction "1_1") (pintype "passive"))
      (node (ref "R9") (pin "1") (pinfunction "1_1") (pintype "passive"))
      (node (ref "SW1") (pin "1") (pinfunction "1_1") (pintype "bidirectional"))
      (node (ref "SW1") (pin "W1") (pinfunction "TAB_W1") (pintype "bidirectional"))
      (node (ref "SW1") (pin "W2") (pinfunction "TAB_W2") (pintype "bidirectional"))
      (node (ref "SW1") (pin "W3") (pinfunction "TAB_W3") (pintype "bidirectional"))
      (node (ref "SW1") (pin "W4") (pinfunction "TAB_W4") (pintype "bidirectional"))
      (node (ref "SW3") (pin "2") (pinfunction "2_2") (pintype "bidirectional"))
      (node (ref "U1") (pin "2") (pinfunction "VSS_2") (pintype "power_in"))
      (node (ref "U16") (pin "13") (pinfunction "DEN_AG_13") (pintype "bidirectional"))
      (node (ref "U16") (pin "14") (pinfunction "GND_14") (pintype "bidirectional"))
      (node (ref "U16") (pin "15") (pinfunction "GND_15") (pintype "bidirectional"))
      (node (ref "U16") (pin "16") (pinfunction "GND_16") (pintype "bidirectional"))
      (node (ref "U16") (pin "17") (pinfunction "GND_17") (pintype "bidirectional"))
      (node (ref "U16") (pin "18") (pinfunction "GND_18") (pintype "bidirectional"))
      (node (ref "U16") (pin "19") (pinfunction "GND_19") (pintype "bidirectional"))
      (node (ref "U16") (pin "20") (pinfunction "GND_20") (pintype "bidirectional"))
      (node (ref "U16") (pin "5") (pinfunction "SDO_AG_5") (pintype "bidirectional"))
      (node (ref "U16") (pin "6") (pinfunction "SDO_M_6") (pintype "bidirectional"))
      (node (ref "U2") (pin "2") (pinfunction "VSS_2") (pintype "bidirectional"))
      (node (ref "U3") (pin "18") (pinfunction "GND1_18") (pintype "bidirectional"))
      (node (ref "U3") (pin "35") (pinfunction "GND2_35") (pintype "bidirectional"))
      (node (ref "U3") (pin "42") (pinfunction "GND3_42") (pintype "bidirectional"))
      (node (ref "U3") (pin "5") (pinfunction "GNDANA_5") (pintype "bidirectional"))
      (node (ref "U3") (pin "EXP") (pinfunction "GND1_EXP") (pintype "bidirectional"))
      (node (ref "U4") (pin "8") (pinfunction "GND_8") (pintype "bidirectional"))
      (node (ref "U4") (pin "PAD") (pinfunction "GND_PAD") (pintype "bidirectional"))
      (node (ref "U5") (pin "18") (pinfunction "GND_18") (pintype "bidirectional"))
      (node (ref "U5") (pin "PAD") (pinfunction "GND_PAD") (pintype "bidirectional"))
      (node (ref "U6") (pin "2") (pinfunction "GND_2") (pintype "bidirectional"))
      (node (ref "U7") (pin "18") (pinfunction "GND_18") (pintype "bidirectional"))
      (node (ref "U7") (pin "PAD") (pinfunction "GND_PAD") (pintype "bidirectional"))
      (node (ref "U8") (pin "2") (pinfunction "GND_2") (pintype "bidirectional"))
      (node (ref "U9") (pin "1") (pinfunction "A0_1") (pintype "bidirectional"))
      (node (ref "U9") (pin "10") (pinfunction "GND_10") (pintype "bidirectional"))
      (node (ref "U9") (pin "11") (pinfunction "INT2_11") (pintype "bidirectional"))
      (node (ref "U9") (pin "14") (pinfunction "INT3_14") (pintype "bidirectional"))
      (node (ref "U9") (pin "2") (pinfunction "A1_2") (pintype "bidirectional"))
      (node (ref "U9") (pin "3") (pinfunction "A2_3") (pintype "bidirectional"))
      (node (ref "U9") (pin "4") (pinfunction "INT0_4") (pintype "bidirectional"))
      (node (ref "U9") (pin "7") (pinfunction "INT1_7") (pintype "bidirectional"))
      (node (ref "U9") (pin "PAD") (pinfunction "GND_PAD") (pintype "bidirectional"))
    )
    (net (code "59") (name "Net-(D2-C)") (class "Default")
      (node (ref "D2") (pin "2") (pinfunction "C_2") (pintype "passive"))
      (node (ref "R3") (pin "1") (pinfunction "1_1") (pintype "passive"))
    )
    (net (code "60") (name "Net-(D3-PadA)") (class "Default")
      (node (ref "D3") (pin "A") (pinfunction "A_A") (pintype "passive"))
      (node (ref "R4") (pin "1") (pinfunction "1_1") (pintype "passive"))
    )
    (net (code "61") (name "Net-(Q1-S)") (class "Default")
      (node (ref "C1") (pin "1") (pinfunction "1_1") (pintype "passive"))
      (node (ref "D1") (pin "C") (pinfunction "C_C") (pintype "passive"))
      (node (ref "Q1") (pin "E") (pinfunction "S_E") (pintype "passive"))
      (node (ref "U1") (pin "1") (pinfunction "VIN_1") (pintype "bidirectional"))
    )
    (net (code "62") (name "Net-(U2-PROG)") (class "Default")
      (node (ref "R1") (pin "1") (pinfunction "1_1") (pintype "passive"))
      (node (ref "U2") (pin "5") (pinfunction "PROG_5") (pintype "bidirectional"))
    )
    (net (code "63") (name "Net-(U2-STAT)") (class "Default")
      (node (ref "R3") (pin "2") (pinfunction "2_2") (pintype "passive"))
      (node (ref "U2") (pin "1") (pinfunction "STAT_1") (pintype "bidirectional"))
    )
    (net (code "64") (name "Net-(U3-PA00)") (class "Default")
      (node (ref "C5") (pin "1") (pinfunction "1_1") (pintype "passive"))
      (node (ref "U3") (pin "1") (pinfunction "PA00_1") (pintype "bidirectional"))
      (node (ref "Y1") (pin "1") (pinfunction "1_1") (pintype "bidirectional"))
    )
    (net (code "65") (name "Net-(U3-PA01)") (class "Default")
      (node (ref "C6") (pin "1") (pinfunction "1_1") (pintype "passive"))
      (node (ref "U3") (pin "2") (pinfunction "PA01_2") (pintype "bidirectional"))
      (node (ref "Y1") (pin "2") (pinfunction "2_2") (pintype "bidirectional"))
    )
    (net (code "66") (name "Net-(U3-VDDCORE)") (class "Default")
      (node (ref "C7") (pin "1") (pinfunction "1_1") (pintype "passive"))
      (node (ref "U3") (pin "43") (pinfunction "VDDCORE_43") (pintype "bidirectional"))
    )
    (net (code "67") (name "Net-(U5-ADECAY)") (class "Default")
      (node (ref "R13") (pin "2") (pinfunction "2_2") (pintype "passive"))
      (node (ref "U5") (pin "24") (pinfunction "ADECAY_24") (pintype "bidirectional"))
    )
    (net (code "68") (name "Net-(U5-AISEN)") (class "Default")
      (node (ref "R11") (pin "2") (pinfunction "2_2") (pintype "passive"))
      (node (ref "U5") (pin "2") (pinfunction "AISEN_2") (pintype "bidirectional"))
    )
    (net (code "69") (name "Net-(U5-AOUT1)") (class "Default")
      (node (ref "J8") (pin "1") (pinfunction "1_1") (pintype "bidirectional"))
      (node (ref "U5") (pin "1") (pinfunction "AOUT1_1") (pintype "bidirectional"))
    )
    (net (code "70") (name "Net-(U5-AOUT2)") (class "Default")
      (node (ref "J8") (pin "2") (pinfunction "2_2") (pintype "bidirectional"))
      (node (ref "U5") (pin "3") (pinfunction "AOUT2_3") (pintype "bidirectional"))
    )
    (net (code "71") (name "Net-(U5-AVREF)") (class "Default")
      (node (ref "U5") (pin "19") (pinfunction "AVREF_19") (pintype "bidirectional"))
      (node (ref "U5") (pin "20") (pinfunction "BVREF_20") (pintype "bidirectional"))
      (node (ref "U6") (pin "5") (pinfunction "W_5") (pintype "bidirectional"))
    )
    (net (code "72") (name "Net-(U5-BDECAY)") (class "Default")
      (node (ref "R12") (pin "2") (pinfunction "2_2") (pintype "passive"))
      (node (ref "U5") (pin "23") (pinfunction "BDECAY_23") (pintype "bidirectional"))
    )
    (net (code "73") (name "Net-(U5-BISEN)") (class "Default")
      (node (ref "R10") (pin "2") (pinfunction "2_2") (pintype "passive"))
      (node (ref "U5") (pin "5") (pinfunction "BISEN_5") (pintype "bidirectional"))
    )
    (net (code "74") (name "Net-(U5-BOUT1)") (class "Default")
      (node (ref "J8") (pin "4") (pinfunction "4_4") (pintype "bidirectional"))
      (node (ref "U5") (pin "6") (pinfunction "BOUT1_6") (pintype "bidirectional"))
    )
    (net (code "75") (name "Net-(U5-BOUT2)") (class "Default")
      (node (ref "J8") (pin "3") (pinfunction "3_3") (pintype "bidirectional"))
      (node (ref "U5") (pin "4") (pinfunction "BOUT2_4") (pintype "bidirectional"))
    )
    (net (code "76") (name "Net-(U5-CONFIG)") (class "Default")
      (node (ref "C15") (pin "1") (pinfunction "1_1") (pintype "passive"))
      (node (ref "U5") (pin "12") (pinfunction "CONFIG_12") (pintype "bidirectional"))
      (node (ref "U5") (pin "17") (pinfunction "VINT_17") (pintype "bidirectional"))
    )
    (net (code "77") (name "Net-(U5-VCP)") (class "Default")
      (node (ref "C14") (pin "1") (pinfunction "1_1") (pintype "passive"))
      (node (ref "U5") (pin "14") (pinfunction "VCP_14") (pintype "bidirectional"))
    )
    (net (code "78") (name "Net-(U5-VREFO)") (class "Default")
      (node (ref "U5") (pin "21") (pinfunction "VREFO_21") (pintype "bidirectional"))
      (node (ref "U6") (pin "6") (pinfunction "A_6") (pintype "bidirectional"))
    )
    (net (code "79") (name "Net-(U7-ADECAY)") (class "Default")
      (node (ref "R18") (pin "2") (pinfunction "2_2") (pintype "passive"))
      (node (ref "U7") (pin "24") (pinfunction "ADECAY_24") (pintype "bidirectional"))
    )
    (net (code "80") (name "Net-(U7-AISEN)") (class "Default")
      (node (ref "R16") (pin "2") (pinfunction "2_2") (pintype "passive"))
      (node (ref "U7") (pin "2") (pinfunction "AISEN_2") (pintype "bidirectional"))
    )
    (net (code "81") (name "Net-(U7-AOUT1)") (class "Default")
      (node (ref "J9") (pin "1") (pinfunction "1_1") (pintype "bidirectional"))
      (node (ref "U7") (pin "1") (pinfunction "AOUT1_1") (pintype "bidirectional"))
    )
    (net (code "82") (name "Net-(U7-AOUT2)") (class "Default")
      (node (ref "J9") (pin "2") (pinfunction "2_2") (pintype "bidirectional"))
      (node (ref "U7") (pin "3") (pinfunction "AOUT2_3") (pintype "bidirectional"))
    )
    (net (code "83") (name "Net-(U7-AVREF)") (class "Default")
      (node (ref "U7") (pin "19") (pinfunction "AVREF_19") (pintype "bidirectional"))
      (node (ref "U7") (pin "20") (pinfunction "BVREF_20") (pintype "bidirectional"))
      (node (ref "U8") (pin "5") (pinfunction "W_5") (pintype "bidirectional"))
    )
    (net (code "84") (name "Net-(U7-BDECAY)") (class "Default")
      (node (ref "R17") (pin "2") (pinfunction "2_2") (pintype "passive"))
      (node (ref "U7") (pin "23") (pinfunction "BDECAY_23") (pintype "bidirectional"))
    )
    (net (code "85") (name "Net-(U7-BISEN)") (class "Default")
      (node (ref "R15") (pin "2") (pinfunction "2_2") (pintype "passive"))
      (node (ref "U7") (pin "5") (pinfunction "BISEN_5") (pintype "bidirectional"))
    )
    (net (code "86") (name "Net-(U7-BOUT1)") (class "Default")
      (node (ref "J9") (pin "4") (pinfunction "4_4") (pintype "bidirectional"))
      (node (ref "U7") (pin "6") (pinfunction "BOUT1_6") (pintype "bidirectional"))
    )
    (net (code "87") (name "Net-(U7-BOUT2)") (class "Default")
      (node (ref "J9") (pin "3") (pinfunction "3_3") (pintype "bidirectional"))
      (node (ref "U7") (pin "4") (pinfunction "BOUT2_4") (pintype "bidirectional"))
    )
    (net (code "88") (name "Net-(U7-CONFIG)") (class "Default")
      (node (ref "C18") (pin "1") (pinfunction "1_1") (pintype "passive"))
      (node (ref "U7") (pin "12") (pinfunction "CONFIG_12") (pintype "bidirectional"))
      (node (ref "U7") (pin "17") (pinfunction "VINT_17") (pintype "bidirectional"))
    )
    (net (code "89") (name "Net-(U7-VCP)") (class "Default")
      (node (ref "C17") (pin "1") (pinfunction "1_1") (pintype "passive"))
      (node (ref "U7") (pin "14") (pinfunction "VCP_14") (pintype "bidirectional"))
    )
    (net (code "90") (name "Net-(U7-VREFO)") (class "Default")
      (node (ref "U7") (pin "21") (pinfunction "VREFO_21") (pintype "bidirectional"))
      (node (ref "U8") (pin "6") (pinfunction "A_6") (pintype "bidirectional"))
    )
    (net (code "91") (name "Net-(U16-C1)") (class "Default")
      (node (ref "C21") (pin "1") (pinfunction "1_1") (pintype "passive"))
      (node (ref "U16") (pin "24") (pinfunction "C1_24") (pintype "bidirectional"))
    )
    (net (code "92") (name "Net-(U16-CAP)") (class "Default")
      (node (ref "C22") (pin "1") (pinfunction "1_1") (pintype "passive"))
      (node (ref "U16") (pin "21") (pinfunction "CAP_21") (pintype "bidirectional"))
    )
    (net (code "93") (name "VBATT") (class "Default")
      (node (ref "C13") (pin "1") (pinfunction "1_1") (pintype "passive"))
      (node (ref "C16") (pin "1") (pinfunction "1_1") (pintype "passive"))
      (node (ref "C2") (pin "1") (pinfunction "1_1") (pintype "passive"))
      (node (ref "J2") (pin "2") (pinfunction "1_2") (pintype "bidirectional"))
      (node (ref "J6") (pin "4") (pinfunction "4_4") (pintype "bidirectional"))
      (node (ref "Q1") (pin "C") (pinfunction "D_C") (pintype "passive"))
      (node (ref "R30") (pin "1") (pinfunction "1_1") (pintype "passive"))
      (node (ref "R8") (pin "2") (pinfunction "2_2") (pintype "passive"))
      (node (ref "SW1") (pin "3") (pinfunction "3_3") (pintype "bidirectional"))
      (node (ref "U2") (pin "3") (pinfunction "VBAT_3") (pintype "bidirectional"))
      (node (ref "U5") (pin "15") (pinfunction "VM_15") (pintype "bidirectional"))
      (node (ref "U5") (pin "16") (pinfunction "VM_16") (pintype "bidirectional"))
      (node (ref "U7") (pin "15") (pinfunction "VM_15") (pintype "bidirectional"))
      (node (ref "U7") (pin "16") (pinfunction "VM_16") (pintype "bidirectional"))
    )
    (net (code "94") (name "VCC") (class "Default")
      (node (ref "C10") (pin "1") (pinfunction "1_1") (pintype "passive"))
      (node (ref "C11") (pin "1") (pinfunction "1_1") (pintype "passive"))
      (node (ref "C12") (pin "1") (pinfunction "1_1") (pintype "passive"))
      (node (ref "C19") (pin "1") (pinfunction "1_1") (pintype "passive"))
      (node (ref "C20") (pin "1") (pinfunction "1_1") (pintype "passive"))
      (node (ref "C25") (pin "1") (pinfunction "1_1") (pintype "passive"))
      (node (ref "C3") (pin "1") (pinfunction "1_1") (pintype "passive"))
      (node (ref "C33") (pin "1") (pinfunction "1_1") (pintype "passive"))
      (node (ref "C34") (pin "1") (pinfunction "1_1") (pintype "passive"))
      (node (ref "C8") (pin "1") (pinfunction "1_1") (pintype "passive"))
      (node (ref "C9") (pin "1") (pinfunction "1_1") (pintype "passive"))
      (node (ref "D4") (pin "C") (pinfunction "C_C") (pintype "passive"))
      (node (ref "J6") (pin "2") (pinfunction "2_2") (pintype "bidirectional"))
      (node (ref "Q2") (pin "E") (pinfunction "S_E") (pintype "passive"))
      (node (ref "R27") (pin "2") (pinfunction "2_2") (pintype "passive"))
      (node (ref "R5") (pin "2") (pinfunction "2_2") (pintype "passive"))
      (node (ref "R6") (pin "2") (pinfunction "2_2") (pintype "passive"))
      (node (ref "R7") (pin "2") (pinfunction "2_2") (pintype "passive"))
      (node (ref "U1") (pin "5") (pinfunction "VOUT_5") (pintype "bidirectional"))
      (node (ref "U16") (pin "1") (pinfunction "VDDIO_1") (pintype "bidirectional"))
      (node (ref "U16") (pin "22") (pinfunction "VDD_22") (pintype "bidirectional"))
      (node (ref "U16") (pin "23") (pinfunction "VDD_23") (pintype "bidirectional"))
      (node (ref "U16") (pin "3") (pinfunction "VDDIO_3") (pintype "bidirectional"))
      (node (ref "U16") (pin "7") (pinfunction "CS_AG_7") (pintype "bidirectional"))
      (node (ref "U16") (pin "8") (pinfunction "CS_M_8") (pintype "bidirectional"))
      (node (ref "U3") (pin "17") (pinfunction "VDDIO1_17") (pintype "bidirectional"))
      (node (ref "U3") (pin "36") (pinfunction "VDDIO2_36") (pintype "bidirectional"))
      (node (ref "U3") (pin "44") (pinfunction "VDDIN_44") (pintype "bidirectional"))
      (node (ref "U3") (pin "6") (pinfunction "VDDANA_6") (pintype "bidirectional"))
      (node (ref "U4") (pin "9") (pinfunction "VCC_9") (pintype "bidirectional"))
      (node (ref "U6") (pin "1") (pinfunction "VDD_1") (pintype "bidirectional"))
      (node (ref "U8") (pin "1") (pinfunction "VDD_1") (pintype "bidirectional"))
      (node (ref "U9") (pin "20") (pinfunction "VCC_20") (pintype "bidirectional"))
    )
    (net (code "95") (name "unconnected-(J1-Pad4)") (class "Default")
      (node (ref "J1") (pin "4") (pinfunction "4_4") (pintype "bidirectional"))
    )
    (net (code "96") (name "unconnected-(U1-NC{slash}GO-Pad4)") (class "Default")
      (node (ref "U1") (pin "4") (pinfunction "NC/GO_4") (pintype "bidirectional"))
    )
    (net (code "97") (name "unconnected-(U4-PA0-Pad5)") (class "Default")
      (node (ref "U4") (pin "5") (pinfunction "PA0_5") (pintype "bidirectional"))
    )
    (net (code "98") (name "unconnected-(U4-PA3-Pad2)") (class "Default")
      (node (ref "U4") (pin "2") (pinfunction "PA3_2") (pintype "bidirectional"))
    )
    (net (code "99") (name "unconnected-(U4-PB0-Pad11)") (class "Default")
      (node (ref "U4") (pin "11") (pinfunction "PB0_11") (pintype "bidirectional"))
    )
    (net (code "100") (name "unconnected-(U4-PB1-Pad12)") (class "Default")
      (node (ref "U4") (pin "12") (pinfunction "PB1_12") (pintype "bidirectional"))
    )
    (net (code "101") (name "unconnected-(U5-M0-Pad10)") (class "Default")
      (node (ref "U5") (pin "10") (pinfunction "M0_10") (pintype "bidirectional"))
    )
    (net (code "102") (name "unconnected-(U5-M1-Pad11)") (class "Default")
      (node (ref "U5") (pin "11") (pinfunction "M1_11") (pintype "bidirectional"))
    )
    (net (code "103") (name "unconnected-(U5-NENBL-Pad7)") (class "Default")
      (node (ref "U5") (pin "7") (pinfunction "NENBL_7") (pintype "bidirectional"))
    )
    (net (code "104") (name "unconnected-(U5-NFAULT-Pad13)") (class "Default")
      (node (ref "U5") (pin "13") (pinfunction "NFAULT_13") (pintype "bidirectional"))
    )
    (net (code "105") (name "unconnected-(U7-M0-Pad10)") (class "Default")
      (node (ref "U7") (pin "10") (pinfunction "M0_10") (pintype "bidirectional"))
    )
    (net (code "106") (name "unconnected-(U7-M1-Pad11)") (class "Default")
      (node (ref "U7") (pin "11") (pinfunction "M1_11") (pintype "bidirectional"))
    )
    (net (code "107") (name "unconnected-(U7-NENBL-Pad7)") (class "Default")
      (node (ref "U7") (pin "7") (pinfunction "NENBL_7") (pintype "bidirectional"))
    )
    (net (code "108") (name "unconnected-(U7-NFAULT-Pad13)") (class "Default")
      (node (ref "U7") (pin "13") (pinfunction "NFAULT_13") (pintype "bidirectional"))
    )
    (net (code "109") (name "unconnected-(U9-INT-Pad17)") (class "Default")
      (node (ref "U9") (pin "17") (pinfunction "INT_17") (pintype "bidirectional"))
    )
    (net (code "110") (name "unconnected-(U16-DRDY_M-Pad9)") (class "Default")
      (node (ref "U16") (pin "9") (pinfunction "DRDY_M_9") (pintype "bidirectional"))
    )
    (net (code "111") (name "unconnected-(U16-INT1_AG-Pad11)") (class "Default")
      (node (ref "U16") (pin "11") (pinfunction "INT1_AG_11") (pintype "bidirectional"))
    )
    (net (code "112") (name "unconnected-(U16-INT2_AG-Pad12)") (class "Default")
      (node (ref "U16") (pin "12") (pinfunction "INT2_AG_12") (pintype "bidirectional"))
    )
    (net (code "113") (name "unconnected-(U16-INT_M-Pad10)") (class "Default")
      (node (ref "U16") (pin "10") (pinfunction "INT_M_10") (pintype "bidirectional"))
    )
  )
)
